# RFID_ver_1_0.net
KiCad netlist of a schematic drawn in EAGLE
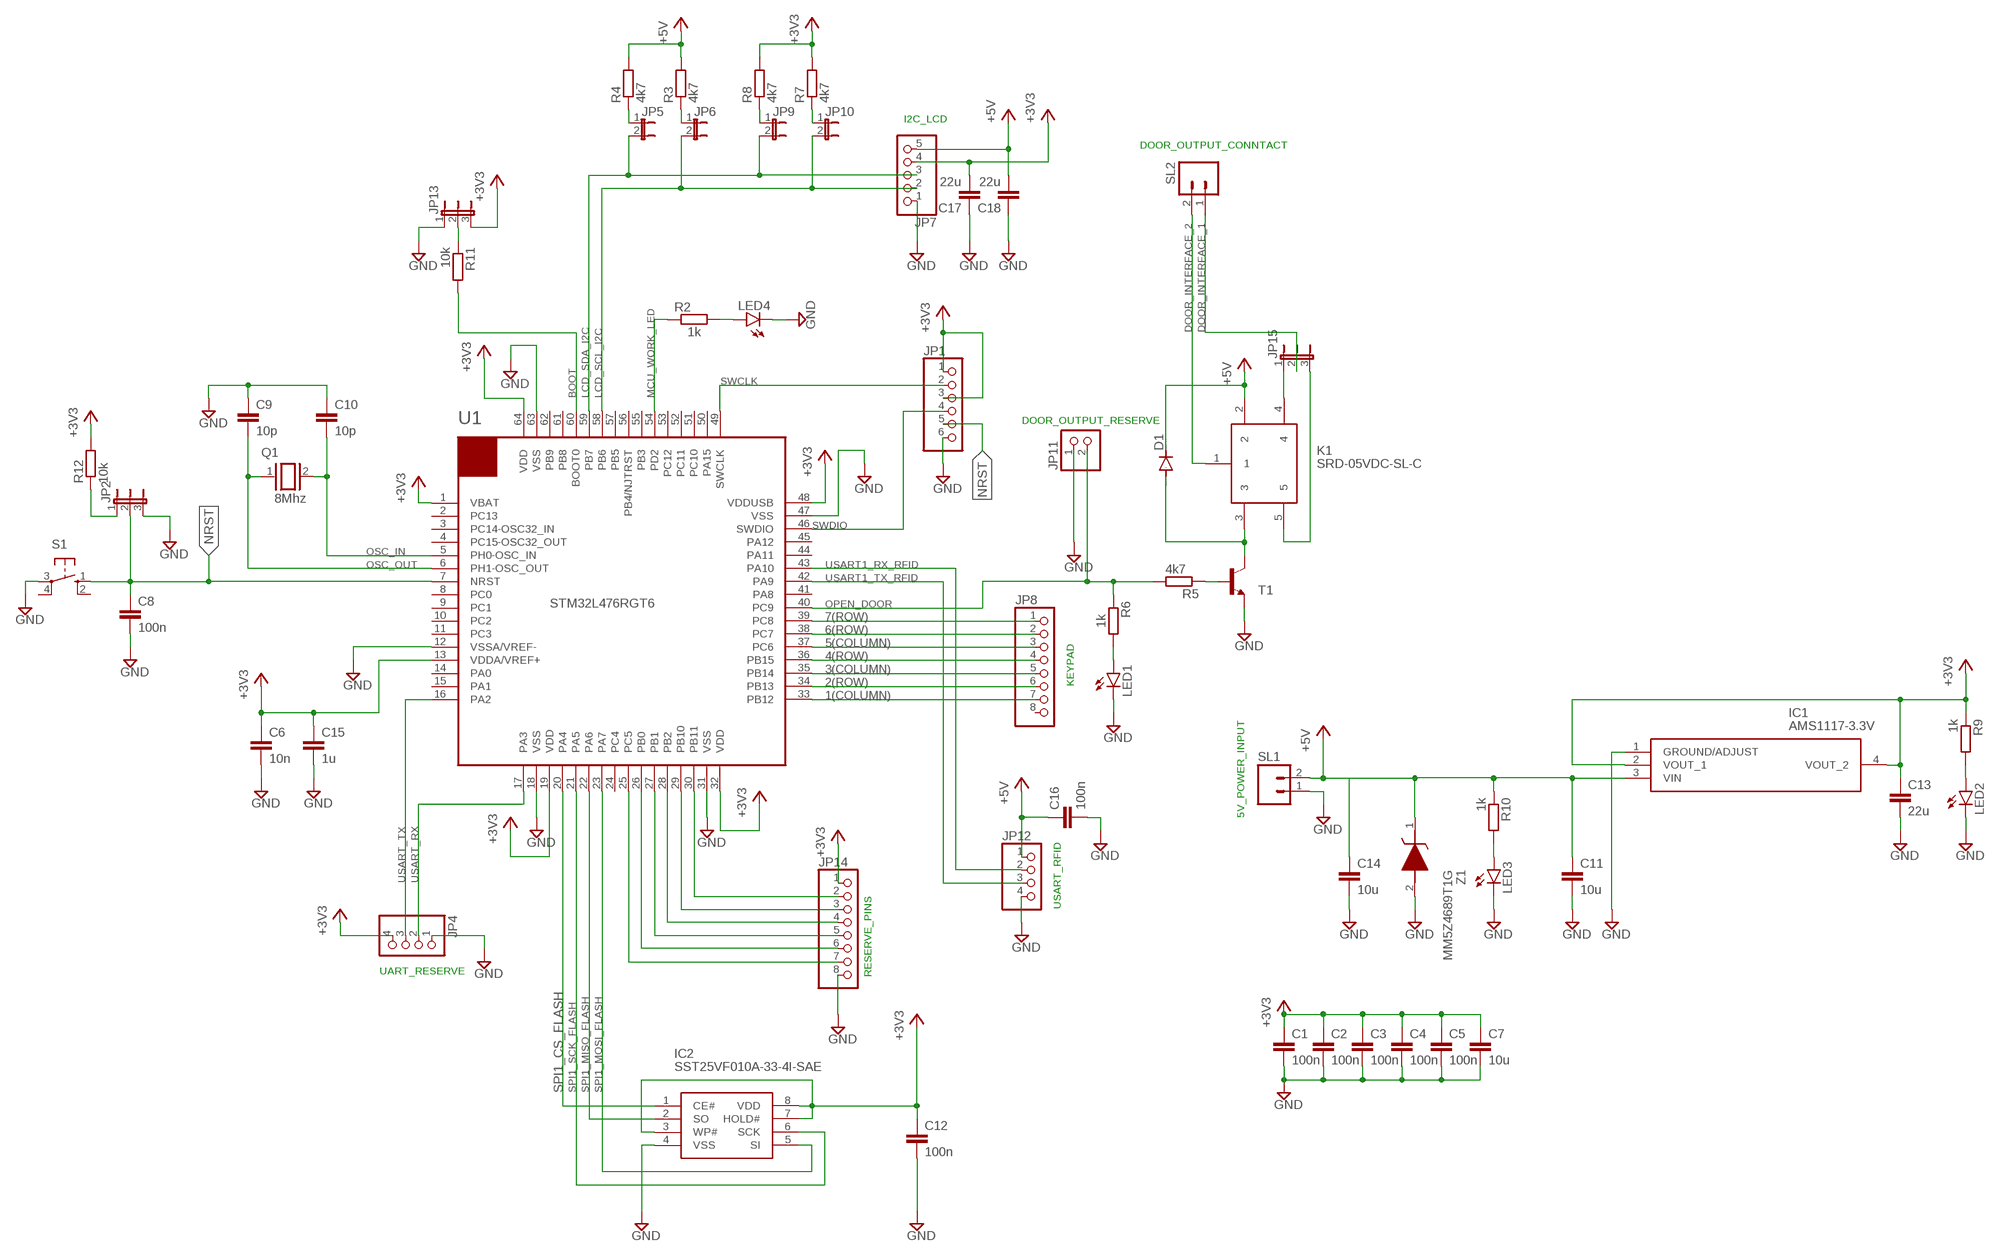
[diagram p0: schematic, sheet 1]

(export (version "E")
  (design (tool "Eeschema 10.0.6"))
  (components
    (comp (ref "C1")
      (value "100n")
      (footprint "eagle-import:C0805")
      (libsource (lib "eagle-import") (part "C-EUC0805"))
    )
    (comp (ref "C2")
      (value "100n")
      (footprint "eagle-import:C0805")
      (libsource (lib "eagle-import") (part "C-EUC0805"))
    )
    (comp (ref "C3")
      (value "100n")
      (footprint "eagle-import:C0805")
      (libsource (lib "eagle-import") (part "C-EUC0805"))
    )
    (comp (ref "C4")
      (value "100n")
      (footprint "eagle-import:C0805")
      (libsource (lib "eagle-import") (part "C-EUC0805"))
    )
    (comp (ref "C5")
      (value "100n")
      (footprint "eagle-import:C0805")
      (libsource (lib "eagle-import") (part "C-EUC0805"))
    )
    (comp (ref "C6")
      (value "10n")
      (footprint "eagle-import:C0805")
      (libsource (lib "eagle-import") (part "C-EUC0805"))
    )
    (comp (ref "C7")
      (value "10u")
      (footprint "eagle-import:C0805")
      (libsource (lib "eagle-import") (part "C-EUC0805"))
    )
    (comp (ref "C8")
      (value "100n")
      (footprint "eagle-import:C0805")
      (libsource (lib "eagle-import") (part "C-EUC0805"))
    )
    (comp (ref "C9")
      (value "10p")
      (footprint "eagle-import:C0805")
      (libsource (lib "eagle-import") (part "C-EUC0805"))
    )
    (comp (ref "C10")
      (value "10p")
      (footprint "eagle-import:C0805")
      (libsource (lib "eagle-import") (part "C-EUC0805"))
    )
    (comp (ref "C11")
      (value "10u")
      (footprint "eagle-import:C0805")
      (libsource (lib "eagle-import") (part "C-EUC0805"))
    )
    (comp (ref "C12")
      (value "100n")
      (footprint "eagle-import:C0805")
      (libsource (lib "eagle-import") (part "C-EUC0805"))
    )
    (comp (ref "C13")
      (value "22u")
      (footprint "eagle-import:C0805")
      (libsource (lib "eagle-import") (part "C-EUC0805"))
    )
    (comp (ref "C14")
      (value "10u")
      (footprint "eagle-import:C0805")
      (libsource (lib "eagle-import") (part "C-EUC0805"))
    )
    (comp (ref "C15")
      (value "1u")
      (footprint "eagle-import:C0805")
      (libsource (lib "eagle-import") (part "C-EUC0805"))
    )
    (comp (ref "C16")
      (value "100n")
      (footprint "eagle-import:C0805")
      (libsource (lib "eagle-import") (part "C-EUC0805"))
    )
    (comp (ref "C17")
      (value "22u")
      (footprint "eagle-import:C0805")
      (libsource (lib "eagle-import") (part "C-EUC0805"))
    )
    (comp (ref "C18")
      (value "22u")
      (footprint "eagle-import:C0805")
      (libsource (lib "eagle-import") (part "C-EUC0805"))
    )
    (comp (ref "D1")
      (value "DIODE-DO-214AC")
      (footprint "eagle-import:DO-214AC")
      (libsource (lib "eagle-import") (part "DIODE-DO-214AC"))
    )
    (comp (ref "IC1")
      (value "AMS1117-3.3V")
      (footprint "eagle-import:SOT229P700X180-4N")
      (fields (field (name "MANUFACTURER_PART_NUMBER") "ams1117-3.3v"))
      (libsource (lib "eagle-import") (part "AMS1117-3.3V"))
    )
    (comp (ref "IC2")
      (value "SST25VF010A-33-4I-SAE")
      (footprint "eagle-import:SOIC127P600X175-8N")
      (fields (field (name "MOUSER_PART_NUMBER") "804-25VF010A3ISAE"))
      (libsource (lib "eagle-import") (part "SST25VF010A-33-4I-SAE"))
    )
    (comp (ref "JP1")
      (value "PINHD-1X6")
      (footprint "eagle-import:1X06")
      (libsource (lib "eagle-import") (part "PINHD-1X6"))
    )
    (comp (ref "JP2")
      (value "JP2E")
      (footprint "eagle-import:JP2")
      (libsource (lib "eagle-import") (part "JP2E"))
    )
    (comp (ref "JP4")
      (value "PINHD-1X4")
      (footprint "eagle-import:1X04")
      (libsource (lib "eagle-import") (part "PINHD-1X4"))
    )
    (comp (ref "JP5")
      (value "JP1E")
      (footprint "eagle-import:JP1")
      (libsource (lib "eagle-import") (part "JP1E"))
    )
    (comp (ref "JP6")
      (value "JP1E")
      (footprint "eagle-import:JP1")
      (libsource (lib "eagle-import") (part "JP1E"))
    )
    (comp (ref "JP7")
      (value "PINHD-1X5")
      (footprint "eagle-import:1X05")
      (libsource (lib "eagle-import") (part "PINHD-1X5"))
    )
    (comp (ref "JP8")
      (value "PINHD-1X8")
      (footprint "eagle-import:1X08")
      (libsource (lib "eagle-import") (part "PINHD-1X8"))
    )
    (comp (ref "JP9")
      (value "JP1E")
      (footprint "eagle-import:JP1")
      (libsource (lib "eagle-import") (part "JP1E"))
    )
    (comp (ref "JP10")
      (value "JP1E")
      (footprint "eagle-import:JP1")
      (libsource (lib "eagle-import") (part "JP1E"))
    )
    (comp (ref "JP11")
      (value "PINHD-1X2")
      (footprint "eagle-import:1X02")
      (libsource (lib "eagle-import") (part "PINHD-1X2"))
    )
    (comp (ref "JP12")
      (value "PINHD-1X4")
      (footprint "eagle-import:1X04")
      (libsource (lib "eagle-import") (part "PINHD-1X4"))
    )
    (comp (ref "JP13")
      (value "JP2E")
      (footprint "eagle-import:JP2")
      (libsource (lib "eagle-import") (part "JP2E"))
    )
    (comp (ref "JP14")
      (value "PINHD-1X8")
      (footprint "eagle-import:1X08")
      (libsource (lib "eagle-import") (part "PINHD-1X8"))
    )
    (comp (ref "JP15")
      (value "JP2E")
      (footprint "eagle-import:JP2")
      (libsource (lib "eagle-import") (part "JP2E"))
    )
    (comp (ref "K1")
      (value "SRD-05VDC-SL-C")
      (footprint "eagle-import:SRD")
      (libsource (lib "eagle-import") (part "SRD-05VDC-SL-C"))
    )
    (comp (ref "LED1")
      (value "LEDCHIP-LED0805")
      (footprint "eagle-import:CHIP-LED0805")
      (libsource (lib "eagle-import") (part "LEDCHIP-LED0805"))
    )
    (comp (ref "LED2")
      (value "LEDCHIP-LED0805")
      (footprint "eagle-import:CHIP-LED0805")
      (libsource (lib "eagle-import") (part "LEDCHIP-LED0805"))
    )
    (comp (ref "LED3")
      (value "LEDCHIP-LED0805")
      (footprint "eagle-import:CHIP-LED0805")
      (libsource (lib "eagle-import") (part "LEDCHIP-LED0805"))
    )
    (comp (ref "LED4")
      (value "LEDCHIP-LED0805")
      (footprint "eagle-import:CHIP-LED0805")
      (libsource (lib "eagle-import") (part "LEDCHIP-LED0805"))
    )
    (comp (ref "Q1")
      (value "8Mhz")
      (footprint "eagle-import:QS")
      (libsource (lib "eagle-import") (part "XTAL/S"))
    )
    (comp (ref "R2")
      (value "1k")
      (footprint "eagle-import:R0805")
      (libsource (lib "eagle-import") (part "R-EU_R0805"))
    )
    (comp (ref "R3")
      (value "4k7")
      (footprint "eagle-import:R0805")
      (libsource (lib "eagle-import") (part "R-EU_R0805"))
    )
    (comp (ref "R4")
      (value "4k7")
      (footprint "eagle-import:R0805")
      (libsource (lib "eagle-import") (part "R-EU_R0805"))
    )
    (comp (ref "R5")
      (value "4k7")
      (footprint "eagle-import:R0805")
      (libsource (lib "eagle-import") (part "R-EU_R0805"))
    )
    (comp (ref "R6")
      (value "1k")
      (footprint "eagle-import:R0805")
      (libsource (lib "eagle-import") (part "R-EU_R0805"))
    )
    (comp (ref "R7")
      (value "4k7")
      (footprint "eagle-import:R0805")
      (libsource (lib "eagle-import") (part "R-EU_R0805"))
    )
    (comp (ref "R8")
      (value "4k7")
      (footprint "eagle-import:R0805")
      (libsource (lib "eagle-import") (part "R-EU_R0805"))
    )
    (comp (ref "R9")
      (value "1k")
      (footprint "eagle-import:R0805")
      (libsource (lib "eagle-import") (part "R-EU_R0805"))
    )
    (comp (ref "R10")
      (value "1k")
      (footprint "eagle-import:R0805")
      (libsource (lib "eagle-import") (part "R-EU_R0805"))
    )
    (comp (ref "R11")
      (value "10k")
      (footprint "eagle-import:R0805")
      (libsource (lib "eagle-import") (part "R-EU_R0805"))
    )
    (comp (ref "R12")
      (value "10k")
      (footprint "eagle-import:R0805")
      (libsource (lib "eagle-import") (part "R-EU_R0805"))
    )
    (comp (ref "S1")
      (value "10-XX")
      (footprint "eagle-import:B3F-10XX")
      (fields (field (name "MPN") "B3F-1000"))
      (libsource (lib "eagle-import") (part "10-XX"))
    )
    (comp (ref "SL1")
      (value "M02")
      (footprint "eagle-import:02P")
      (libsource (lib "eagle-import") (part "M02"))
    )
    (comp (ref "SL2")
      (value "M02")
      (footprint "eagle-import:02P")
      (libsource (lib "eagle-import") (part "M02"))
    )
    (comp (ref "T1")
      (value "BC817-NPN-SOT23-BEC")
      (footprint "eagle-import:SOT23-BEC")
      (libsource (lib "eagle-import") (part "-NPN-SOT23-BECBC817"))
    )
    (comp (ref "U1")
      (value "STM32L476RGT6")
      (footprint "eagle-import:LQFP-64")
      (libsource (lib "eagle-import") (part "STM32L476RT6G"))
    )
    (comp (ref "Z1")
      (value "MM5Z4689T1G")
      (footprint "eagle-import:SODFL1608X70N")
      (fields (field (name "MOUSER_PART_NUMBER") "863-MM5Z4689T1G"))
      (libsource (lib "eagle-import") (part "MM5Z4689T1G"))
    )
  )
  (nets
    (net (code "1") (name "+3V3") (class "Default")
      (node (ref "C1") (pin "1") (pinfunction "1_1") (pintype "passive"))
      (node (ref "C12") (pin "1") (pinfunction "1_1") (pintype "passive"))
      (node (ref "C13") (pin "1") (pinfunction "1_1") (pintype "passive"))
      (node (ref "C15") (pin "1") (pinfunction "1_1") (pintype "passive"))
      (node (ref "C17") (pin "2") (pinfunction "2_2") (pintype "passive"))
      (node (ref "C2") (pin "1") (pinfunction "1_1") (pintype "passive"))
      (node (ref "C3") (pin "1") (pinfunction "1_1") (pintype "passive"))
      (node (ref "C4") (pin "1") (pinfunction "1_1") (pintype "passive"))
      (node (ref "C5") (pin "1") (pinfunction "1_1") (pintype "passive"))
      (node (ref "C6") (pin "1") (pinfunction "1_1") (pintype "passive"))
      (node (ref "C7") (pin "1") (pinfunction "1_1") (pintype "passive"))
      (node (ref "IC1") (pin "2") (pinfunction "VOUT_1_2") (pintype "bidirectional"))
      (node (ref "IC1") (pin "4") (pinfunction "VOUT_2_4") (pintype "bidirectional"))
      (node (ref "IC2") (pin "3") (pinfunction "WP#_3") (pintype "bidirectional"))
      (node (ref "IC2") (pin "7") (pinfunction "HOLD#_7") (pintype "bidirectional"))
      (node (ref "IC2") (pin "8") (pinfunction "VDD_8") (pintype "bidirectional"))
      (node (ref "JP1") (pin "1") (pinfunction "1_1") (pintype "passive"))
      (node (ref "JP1") (pin "3") (pinfunction "3_3") (pintype "passive"))
      (node (ref "JP13") (pin "3") (pinfunction "3_3") (pintype "passive"))
      (node (ref "JP14") (pin "1") (pinfunction "1_1") (pintype "passive"))
      (node (ref "JP4") (pin "4") (pinfunction "4_4") (pintype "passive"))
      (node (ref "JP7") (pin "4") (pinfunction "4_4") (pintype "passive"))
      (node (ref "R12") (pin "2") (pinfunction "2_2") (pintype "passive"))
      (node (ref "R7") (pin "2") (pinfunction "2_2") (pintype "passive"))
      (node (ref "R8") (pin "2") (pinfunction "2_2") (pintype "passive"))
      (node (ref "R9") (pin "1") (pinfunction "1_1") (pintype "passive"))
      (node (ref "U1") (pin "1") (pinfunction "VBAT_1") (pintype "power_in"))
      (node (ref "U1") (pin "13") (pinfunction "VDDA/VREF+_13") (pintype "power_in"))
      (node (ref "U1") (pin "19") (pinfunction "VDD_19") (pintype "power_in"))
      (node (ref "U1") (pin "32") (pinfunction "VDD_32") (pintype "power_in"))
      (node (ref "U1") (pin "48") (pinfunction "VDDUSB_48") (pintype "power_in"))
      (node (ref "U1") (pin "64") (pinfunction "VDD_64") (pintype "power_in"))
    )
    (net (code "2") (name "+5V") (class "Default")
      (node (ref "C11") (pin "1") (pinfunction "1_1") (pintype "passive"))
      (node (ref "C16") (pin "1") (pinfunction "1_1") (pintype "passive"))
      (node (ref "C18") (pin "2") (pinfunction "2_2") (pintype "passive"))
      (node (ref "D1") (pin "C") (pinfunction "C_C") (pintype "passive"))
      (node (ref "IC1") (pin "3") (pinfunction "VIN_3") (pintype "bidirectional"))
      (node (ref "JP12") (pin "1") (pinfunction "1_1") (pintype "passive"))
      (node (ref "JP7") (pin "5") (pinfunction "5_5") (pintype "passive"))
      (node (ref "K1") (pin "2") (pinfunction "2_2") (pintype "bidirectional"))
      (node (ref "R10") (pin "1") (pinfunction "1_1") (pintype "passive"))
      (node (ref "R3") (pin "2") (pinfunction "2_2") (pintype "passive"))
      (node (ref "R4") (pin "2") (pinfunction "2_2") (pintype "passive"))
      (node (ref "SL1") (pin "2") (pinfunction "2_2") (pintype "passive"))
      (node (ref "Z1") (pin "1") (pinfunction "K_1") (pintype "bidirectional"))
    )
    (net (code "3") (name "/1(COLUMN)") (class "Default")
      (node (ref "JP8") (pin "7") (pinfunction "7_7") (pintype "passive"))
      (node (ref "U1") (pin "33") (pinfunction "PB12_33") (pintype "bidirectional"))
    )
    (net (code "4") (name "/2(ROW)") (class "Default")
      (node (ref "JP8") (pin "6") (pinfunction "6_6") (pintype "passive"))
      (node (ref "U1") (pin "34") (pinfunction "PB13_34") (pintype "bidirectional"))
    )
    (net (code "5") (name "/3(COLUMN)") (class "Default")
      (node (ref "JP8") (pin "5") (pinfunction "5_5") (pintype "passive"))
      (node (ref "U1") (pin "35") (pinfunction "PB14_35") (pintype "bidirectional"))
    )
    (net (code "6") (name "/4(ROW)") (class "Default")
      (node (ref "JP8") (pin "4") (pinfunction "4_4") (pintype "passive"))
      (node (ref "U1") (pin "36") (pinfunction "PB15_36") (pintype "bidirectional"))
    )
    (net (code "7") (name "/5(COLUMN)") (class "Default")
      (node (ref "JP8") (pin "3") (pinfunction "3_3") (pintype "passive"))
      (node (ref "U1") (pin "37") (pinfunction "PC6_37") (pintype "bidirectional"))
    )
    (net (code "8") (name "/6(ROW)") (class "Default")
      (node (ref "JP8") (pin "2") (pinfunction "2_2") (pintype "passive"))
      (node (ref "U1") (pin "38") (pinfunction "PC7_38") (pintype "bidirectional"))
    )
    (net (code "9") (name "/7(ROW)") (class "Default")
      (node (ref "JP8") (pin "1") (pinfunction "1_1") (pintype "passive"))
      (node (ref "U1") (pin "39") (pinfunction "PC8_39") (pintype "bidirectional"))
    )
    (net (code "10") (name "/BOOT") (class "Default")
      (node (ref "R11") (pin "2") (pinfunction "2_2") (pintype "passive"))
      (node (ref "U1") (pin "60") (pinfunction "BOOT0_60") (pintype "input"))
    )
    (net (code "11") (name "/DOOR_INTERFACE_1") (class "Default")
      (node (ref "JP15") (pin "2") (pinfunction "2_2") (pintype "passive"))
      (node (ref "SL2") (pin "1") (pinfunction "1_1") (pintype "passive"))
    )
    (net (code "12") (name "/DOOR_INTERFACE_2") (class "Default")
      (node (ref "K1") (pin "1") (pinfunction "1_1") (pintype "bidirectional"))
      (node (ref "SL2") (pin "2") (pinfunction "2_2") (pintype "passive"))
    )
    (net (code "13") (name "/LCD_SCL_I2C") (class "Default")
      (node (ref "JP10") (pin "2") (pinfunction "2_2") (pintype "passive"))
      (node (ref "JP6") (pin "2") (pinfunction "2_2") (pintype "passive"))
      (node (ref "JP7") (pin "2") (pinfunction "2_2") (pintype "passive"))
      (node (ref "U1") (pin "58") (pinfunction "PB6_58") (pintype "bidirectional"))
    )
    (net (code "14") (name "/LCD_SDA_I2C") (class "Default")
      (node (ref "JP5") (pin "2") (pinfunction "2_2") (pintype "passive"))
      (node (ref "JP7") (pin "3") (pinfunction "3_3") (pintype "passive"))
      (node (ref "JP9") (pin "2") (pinfunction "2_2") (pintype "passive"))
      (node (ref "U1") (pin "59") (pinfunction "PB7_59") (pintype "bidirectional"))
    )
    (net (code "15") (name "/MCU_WORK_LED") (class "Default")
      (node (ref "R2") (pin "1") (pinfunction "1_1") (pintype "passive"))
      (node (ref "U1") (pin "54") (pinfunction "PD2_54") (pintype "bidirectional"))
    )
    (net (code "16") (name "/OPEN_DOOR") (class "Default")
      (node (ref "JP11") (pin "2") (pinfunction "2_2") (pintype "passive"))
      (node (ref "R5") (pin "2") (pinfunction "2_2") (pintype "passive"))
      (node (ref "R6") (pin "1") (pinfunction "1_1") (pintype "passive"))
      (node (ref "U1") (pin "40") (pinfunction "PC9_40") (pintype "bidirectional"))
    )
    (net (code "17") (name "/OSC_IN") (class "Default")
      (node (ref "C10") (pin "2") (pinfunction "2_2") (pintype "passive"))
      (node (ref "Q1") (pin "2") (pinfunction "2_2") (pintype "passive"))
      (node (ref "U1") (pin "5") (pinfunction "PH0-OSC_IN_5") (pintype "bidirectional"))
    )
    (net (code "18") (name "/OSC_OUT") (class "Default")
      (node (ref "C9") (pin "2") (pinfunction "2_2") (pintype "passive"))
      (node (ref "Q1") (pin "1") (pinfunction "1_1") (pintype "passive"))
      (node (ref "U1") (pin "6") (pinfunction "PH1-OSC_OUT_6") (pintype "bidirectional"))
    )
    (net (code "19") (name "/SPI1_CS_FLASH") (class "Default")
      (node (ref "IC2") (pin "1") (pinfunction "CE#_1") (pintype "bidirectional"))
      (node (ref "U1") (pin "20") (pinfunction "PA4_20") (pintype "bidirectional"))
    )
    (net (code "20") (name "/SPI1_MISO_FLASH") (class "Default")
      (node (ref "IC2") (pin "2") (pinfunction "SO_2") (pintype "bidirectional"))
      (node (ref "U1") (pin "22") (pinfunction "PA6_22") (pintype "bidirectional"))
    )
    (net (code "21") (name "/SPI1_MOSI_FLASH") (class "Default")
      (node (ref "IC2") (pin "5") (pinfunction "SI_5") (pintype "bidirectional"))
      (node (ref "U1") (pin "23") (pinfunction "PA7_23") (pintype "bidirectional"))
    )
    (net (code "22") (name "/SPI1_SCK_FLASH") (class "Default")
      (node (ref "IC2") (pin "6") (pinfunction "SCK_6") (pintype "bidirectional"))
      (node (ref "U1") (pin "21") (pinfunction "PA5_21") (pintype "bidirectional"))
    )
    (net (code "23") (name "/SWCLK") (class "Default")
      (node (ref "JP1") (pin "2") (pinfunction "2_2") (pintype "passive"))
      (node (ref "U1") (pin "49") (pinfunction "SWCLK_49") (pintype "bidirectional"))
    )
    (net (code "24") (name "/SWDIO") (class "Default")
      (node (ref "JP1") (pin "4") (pinfunction "4_4") (pintype "passive"))
      (node (ref "U1") (pin "46") (pinfunction "SWDIO_46") (pintype "bidirectional"))
    )
    (net (code "25") (name "/USART1_RX_RFID") (class "Default")
      (node (ref "JP12") (pin "2") (pinfunction "2_2") (pintype "passive"))
      (node (ref "U1") (pin "43") (pinfunction "PA10_43") (pintype "bidirectional"))
    )
    (net (code "26") (name "/USART1_TX_RFID") (class "Default")
      (node (ref "JP12") (pin "3") (pinfunction "3_3") (pintype "passive"))
      (node (ref "U1") (pin "42") (pinfunction "PA9_42") (pintype "bidirectional"))
    )
    (net (code "27") (name "/USART_RX") (class "Default")
      (node (ref "JP4") (pin "2") (pinfunction "2_2") (pintype "passive"))
      (node (ref "U1") (pin "17") (pinfunction "PA3_17") (pintype "bidirectional"))
    )
    (net (code "28") (name "/USART_TX") (class "Default")
      (node (ref "JP4") (pin "3") (pinfunction "3_3") (pintype "passive"))
      (node (ref "U1") (pin "16") (pinfunction "PA2_16") (pintype "bidirectional"))
    )
    (net (code "29") (name "GND") (class "Default")
      (node (ref "C1") (pin "2") (pinfunction "2_2") (pintype "passive"))
      (node (ref "C10") (pin "1") (pinfunction "1_1") (pintype "passive"))
      (node (ref "C11") (pin "2") (pinfunction "2_2") (pintype "passive"))
      (node (ref "C12") (pin "2") (pinfunction "2_2") (pintype "passive"))
      (node (ref "C13") (pin "2") (pinfunction "2_2") (pintype "passive"))
      (node (ref "C14") (pin "2") (pinfunction "2_2") (pintype "passive"))
      (node (ref "C15") (pin "2") (pinfunction "2_2") (pintype "passive"))
      (node (ref "C16") (pin "2") (pinfunction "2_2") (pintype "passive"))
      (node (ref "C17") (pin "1") (pinfunction "1_1") (pintype "passive"))
      (node (ref "C18") (pin "1") (pinfunction "1_1") (pintype "passive"))
      (node (ref "C2") (pin "2") (pinfunction "2_2") (pintype "passive"))
      (node (ref "C3") (pin "2") (pinfunction "2_2") (pintype "passive"))
      (node (ref "C4") (pin "2") (pinfunction "2_2") (pintype "passive"))
      (node (ref "C5") (pin "2") (pinfunction "2_2") (pintype "passive"))
      (node (ref "C6") (pin "2") (pinfunction "2_2") (pintype "passive"))
      (node (ref "C7") (pin "2") (pinfunction "2_2") (pintype "passive"))
      (node (ref "C8") (pin "2") (pinfunction "2_2") (pintype "passive"))
      (node (ref "C9") (pin "1") (pinfunction "1_1") (pintype "passive"))
      (node (ref "IC1") (pin "1") (pinfunction "GROUND/ADJUST_1") (pintype "bidirectional"))
      (node (ref "IC2") (pin "4") (pinfunction "VSS_4") (pintype "bidirectional"))
      (node (ref "JP1") (pin "6") (pinfunction "6_6") (pintype "passive"))
      (node (ref "JP11") (pin "1") (pinfunction "1_1") (pintype "passive"))
      (node (ref "JP12") (pin "4") (pinfunction "4_4") (pintype "passive"))
      (node (ref "JP13") (pin "1") (pinfunction "1_1") (pintype "passive"))
      (node (ref "JP14") (pin "8") (pinfunction "8_8") (pintype "passive"))
      (node (ref "JP2") (pin "3") (pinfunction "3_3") (pintype "passive"))
      (node (ref "JP4") (pin "1") (pinfunction "1_1") (pintype "passive"))
      (node (ref "JP7") (pin "1") (pinfunction "1_1") (pintype "passive"))
      (node (ref "LED1") (pin "C") (pinfunction "C_C") (pintype "passive"))
      (node (ref "LED2") (pin "C") (pinfunction "C_C") (pintype "passive"))
      (node (ref "LED3") (pin "C") (pinfunction "C_C") (pintype "passive"))
      (node (ref "LED4") (pin "C") (pinfunction "C_C") (pintype "passive"))
      (node (ref "S1") (pin "3") (pinfunction "P_3") (pintype "passive"))
      (node (ref "SL1") (pin "1") (pinfunction "1_1") (pintype "passive"))
      (node (ref "T1") (pin "E") (pinfunction "E_E") (pintype "passive"))
      (node (ref "U1") (pin "12") (pinfunction "VSSA/VREF-_12") (pintype "power_in"))
      (node (ref "U1") (pin "18") (pinfunction "VSS_18") (pintype "power_in"))
      (node (ref "U1") (pin "31") (pinfunction "VSS_31") (pintype "power_in"))
      (node (ref "U1") (pin "47") (pinfunction "VSS_47") (pintype "power_in"))
      (node (ref "U1") (pin "63") (pinfunction "VSS_63") (pintype "power_in"))
      (node (ref "Z1") (pin "2") (pinfunction "A_2") (pintype "bidirectional"))
    )
    (net (code "30") (name "NRST") (class "Default")
      (node (ref "C8") (pin "1") (pinfunction "1_1") (pintype "passive"))
      (node (ref "JP1") (pin "5") (pinfunction "5_5") (pintype "passive"))
      (node (ref "JP2") (pin "2") (pinfunction "2_2") (pintype "passive"))
      (node (ref "S1") (pin "1") (pinfunction "S_1") (pintype "passive"))
      (node (ref "U1") (pin "7") (pinfunction "NRST_7") (pintype "bidirectional"))
    )
    (net (code "31") (name "Net-(D1-PadA)") (class "Default")
      (node (ref "D1") (pin "A") (pinfunction "A_A") (pintype "passive"))
      (node (ref "K1") (pin "3") (pinfunction "3_3") (pintype "bidirectional"))
      (node (ref "T1") (pin "C") (pinfunction "C_C") (pintype "passive"))
    )
    (net (code "32") (name "Net-(JP2-Pad1)") (class "Default")
      (node (ref "JP2") (pin "1") (pinfunction "1_1") (pintype "passive"))
      (node (ref "R12") (pin "1") (pinfunction "1_1") (pintype "passive"))
    )
    (net (code "33") (name "Net-(JP5-Pad1)") (class "Default")
      (node (ref "JP5") (pin "1") (pinfunction "1_1") (pintype "passive"))
      (node (ref "R4") (pin "1") (pinfunction "1_1") (pintype "passive"))
    )
    (net (code "34") (name "Net-(JP6-Pad1)") (class "Default")
      (node (ref "JP6") (pin "1") (pinfunction "1_1") (pintype "passive"))
      (node (ref "R3") (pin "1") (pinfunction "1_1") (pintype "passive"))
    )
    (net (code "35") (name "Net-(JP9-Pad1)") (class "Default")
      (node (ref "JP9") (pin "1") (pinfunction "1_1") (pintype "passive"))
      (node (ref "R8") (pin "1") (pinfunction "1_1") (pintype "passive"))
    )
    (net (code "36") (name "Net-(JP10-Pad1)") (class "Default")
      (node (ref "JP10") (pin "1") (pinfunction "1_1") (pintype "passive"))
      (node (ref "R7") (pin "1") (pinfunction "1_1") (pintype "passive"))
    )
    (net (code "37") (name "Net-(JP13-Pad2)") (class "Default")
      (node (ref "JP13") (pin "2") (pinfunction "2_2") (pintype "passive"))
      (node (ref "R11") (pin "1") (pinfunction "1_1") (pintype "passive"))
    )
    (net (code "38") (name "Net-(JP15-Pad1)") (class "Default")
      (node (ref "JP15") (pin "1") (pinfunction "1_1") (pintype "passive"))
      (node (ref "K1") (pin "4") (pinfunction "4_4") (pintype "bidirectional"))
    )
    (net (code "39") (name "Net-(JP15-Pad3)") (class "Default")
      (node (ref "JP15") (pin "3") (pinfunction "3_3") (pintype "passive"))
      (node (ref "K1") (pin "5") (pinfunction "5_5") (pintype "bidirectional"))
    )
    (net (code "40") (name "Net-(LED1-PadA)") (class "Default")
      (node (ref "LED1") (pin "A") (pinfunction "A_A") (pintype "passive"))
      (node (ref "R6") (pin "2") (pinfunction "2_2") (pintype "passive"))
    )
    (net (code "41") (name "Net-(LED2-PadA)") (class "Default")
      (node (ref "LED2") (pin "A") (pinfunction "A_A") (pintype "passive"))
      (node (ref "R9") (pin "2") (pinfunction "2_2") (pintype "passive"))
    )
    (net (code "42") (name "Net-(LED3-PadA)") (class "Default")
      (node (ref "LED3") (pin "A") (pinfunction "A_A") (pintype "passive"))
      (node (ref "R10") (pin "2") (pinfunction "2_2") (pintype "passive"))
    )
    (net (code "43") (name "Net-(LED4-PadA)") (class "Default")
      (node (ref "LED4") (pin "A") (pinfunction "A_A") (pintype "passive"))
      (node (ref "R2") (pin "2") (pinfunction "2_2") (pintype "passive"))
    )
    (net (code "44") (name "Net-(R5-Pad1)") (class "Default")
      (node (ref "R5") (pin "1") (pinfunction "1_1") (pintype "passive"))
      (node (ref "T1") (pin "B") (pinfunction "B_B") (pintype "passive"))
    )
    (net (code "45") (name "Net-(U1-PB0)") (class "Default")
      (node (ref "JP14") (pin "6") (pinfunction "6_6") (pintype "passive"))
      (node (ref "U1") (pin "26") (pinfunction "PB0_26") (pintype "bidirectional"))
    )
    (net (code "46") (name "Net-(U1-PB1)") (class "Default")
      (node (ref "JP14") (pin "5") (pinfunction "5_5") (pintype "passive"))
      (node (ref "U1") (pin "27") (pinfunction "PB1_27") (pintype "bidirectional"))
    )
    (net (code "47") (name "Net-(U1-PB2)") (class "Default")
      (node (ref "JP14") (pin "4") (pinfunction "4_4") (pintype "passive"))
      (node (ref "U1") (pin "28") (pinfunction "PB2_28") (pintype "bidirectional"))
    )
    (net (code "48") (name "Net-(U1-PB10)") (class "Default")
      (node (ref "JP14") (pin "3") (pinfunction "3_3") (pintype "passive"))
      (node (ref "U1") (pin "29") (pinfunction "PB10_29") (pintype "bidirectional"))
    )
    (net (code "49") (name "Net-(U1-PB11)") (class "Default")
      (node (ref "JP14") (pin "2") (pinfunction "2_2") (pintype "passive"))
      (node (ref "U1") (pin "30") (pinfunction "PB11_30") (pintype "bidirectional"))
    )
    (net (code "50") (name "Net-(U1-PC5)") (class "Default")
      (node (ref "JP14") (pin "7") (pinfunction "7_7") (pintype "passive"))
      (node (ref "U1") (pin "25") (pinfunction "PC5_25") (pintype "bidirectional"))
    )
    (net (code "51") (name "unconnected-(C14-Pad1)") (class "Default")
      (node (ref "C14") (pin "1") (pinfunction "1_1") (pintype "passive"))
    )
    (net (code "52") (name "unconnected-(JP8-Pad8)") (class "Default")
      (node (ref "JP8") (pin "8") (pinfunction "8_8") (pintype "passive"))
    )
    (net (code "53") (name "unconnected-(S1-P1-Pad4)") (class "Default")
      (node (ref "S1") (pin "4") (pinfunction "P1_4") (pintype "passive"))
    )
    (net (code "54") (name "unconnected-(S1-S1-Pad2)") (class "Default")
      (node (ref "S1") (pin "2") (pinfunction "S1_2") (pintype "passive"))
    )
    (net (code "55") (name "unconnected-(U1-PA0-Pad14)") (class "Default")
      (node (ref "U1") (pin "14") (pinfunction "PA0_14") (pintype "bidirectional"))
    )
    (net (code "56") (name "unconnected-(U1-PA1-Pad15)") (class "Default")
      (node (ref "U1") (pin "15") (pinfunction "PA1_15") (pintype "bidirectional"))
    )
    (net (code "57") (name "unconnected-(U1-PA8-Pad41)") (class "Default")
      (node (ref "U1") (pin "41") (pinfunction "PA8_41") (pintype "bidirectional"))
    )
    (net (code "58") (name "unconnected-(U1-PA11-Pad44)") (class "Default")
      (node (ref "U1") (pin "44") (pinfunction "PA11_44") (pintype "bidirectional"))
    )
    (net (code "59") (name "unconnected-(U1-PA12-Pad45)") (class "Default")
      (node (ref "U1") (pin "45") (pinfunction "PA12_45") (pintype "bidirectional"))
    )
    (net (code "60") (name "unconnected-(U1-PA15-Pad50)") (class "Default")
      (node (ref "U1") (pin "50") (pinfunction "PA15_50") (pintype "bidirectional"))
    )
    (net (code "61") (name "unconnected-(U1-PB3-Pad55)") (class "Default")
      (node (ref "U1") (pin "55") (pinfunction "PB3_55") (pintype "bidirectional"))
    )
    (net (code "62") (name "unconnected-(U1-PB4{slash}NJTRST-Pad56)") (class "Default")
      (node (ref "U1") (pin "56") (pinfunction "PB4/NJTRST_56") (pintype "bidirectional"))
    )
    (net (code "63") (name "unconnected-(U1-PB5-Pad57)") (class "Default")
      (node (ref "U1") (pin "57") (pinfunction "PB5_57") (pintype "bidirectional"))
    )
    (net (code "64") (name "unconnected-(U1-PB8-Pad61)") (class "Default")
      (node (ref "U1") (pin "61") (pinfunction "PB8_61") (pintype "bidirectional"))
    )
    (net (code "65") (name "unconnected-(U1-PB9-Pad62)") (class "Default")
      (node (ref "U1") (pin "62") (pinfunction "PB9_62") (pintype "bidirectional"))
    )
    (net (code "66") (name "unconnected-(U1-PC0-Pad8)") (class "Default")
      (node (ref "U1") (pin "8") (pinfunction "PC0_8") (pintype "bidirectional"))
    )
    (net (code "67") (name "unconnected-(U1-PC1-Pad9)") (class "Default")
      (node (ref "U1") (pin "9") (pinfunction "PC1_9") (pintype "bidirectional"))
    )
    (net (code "68") (name "unconnected-(U1-PC2-Pad10)") (class "Default")
      (node (ref "U1") (pin "10") (pinfunction "PC2_10") (pintype "bidirectional"))
    )
    (net (code "69") (name "unconnected-(U1-PC3-Pad11)") (class "Default")
      (node (ref "U1") (pin "11") (pinfunction "PC3_11") (pintype "bidirectional"))
    )
    (net (code "70") (name "unconnected-(U1-PC4-Pad24)") (class "Default")
      (node (ref "U1") (pin "24") (pinfunction "PC4_24") (pintype "bidirectional"))
    )
    (net (code "71") (name "unconnected-(U1-PC10-Pad51)") (class "Default")
      (node (ref "U1") (pin "51") (pinfunction "PC10_51") (pintype "bidirectional"))
    )
    (net (code "72") (name "unconnected-(U1-PC11-Pad52)") (class "Default")
      (node (ref "U1") (pin "52") (pinfunction "PC11_52") (pintype "bidirectional"))
    )
    (net (code "73") (name "unconnected-(U1-PC12-Pad53)") (class "Default")
      (node (ref "U1") (pin "53") (pinfunction "PC12_53") (pintype "bidirectional"))
    )
    (net (code "74") (name "unconnected-(U1-PC13-Pad2)") (class "Default")
      (node (ref "U1") (pin "2") (pinfunction "PC13_2") (pintype "bidirectional"))
    )
    (net (code "75") (name "unconnected-(U1-PC14-OSC32_IN-Pad3)") (class "Default")
      (node (ref "U1") (pin "3") (pinfunction "PC14-OSC32_IN_3") (pintype "bidirectional"))
    )
    (net (code "76") (name "unconnected-(U1-PC15-OSC32_OUT-Pad4)") (class "Default")
      (node (ref "U1") (pin "4") (pinfunction "PC15-OSC32_OUT_4") (pintype "bidirectional"))
    )
  )
)
